# hw_system_switch.net
KiCad netlist of a schematic drawn in Altium Designer
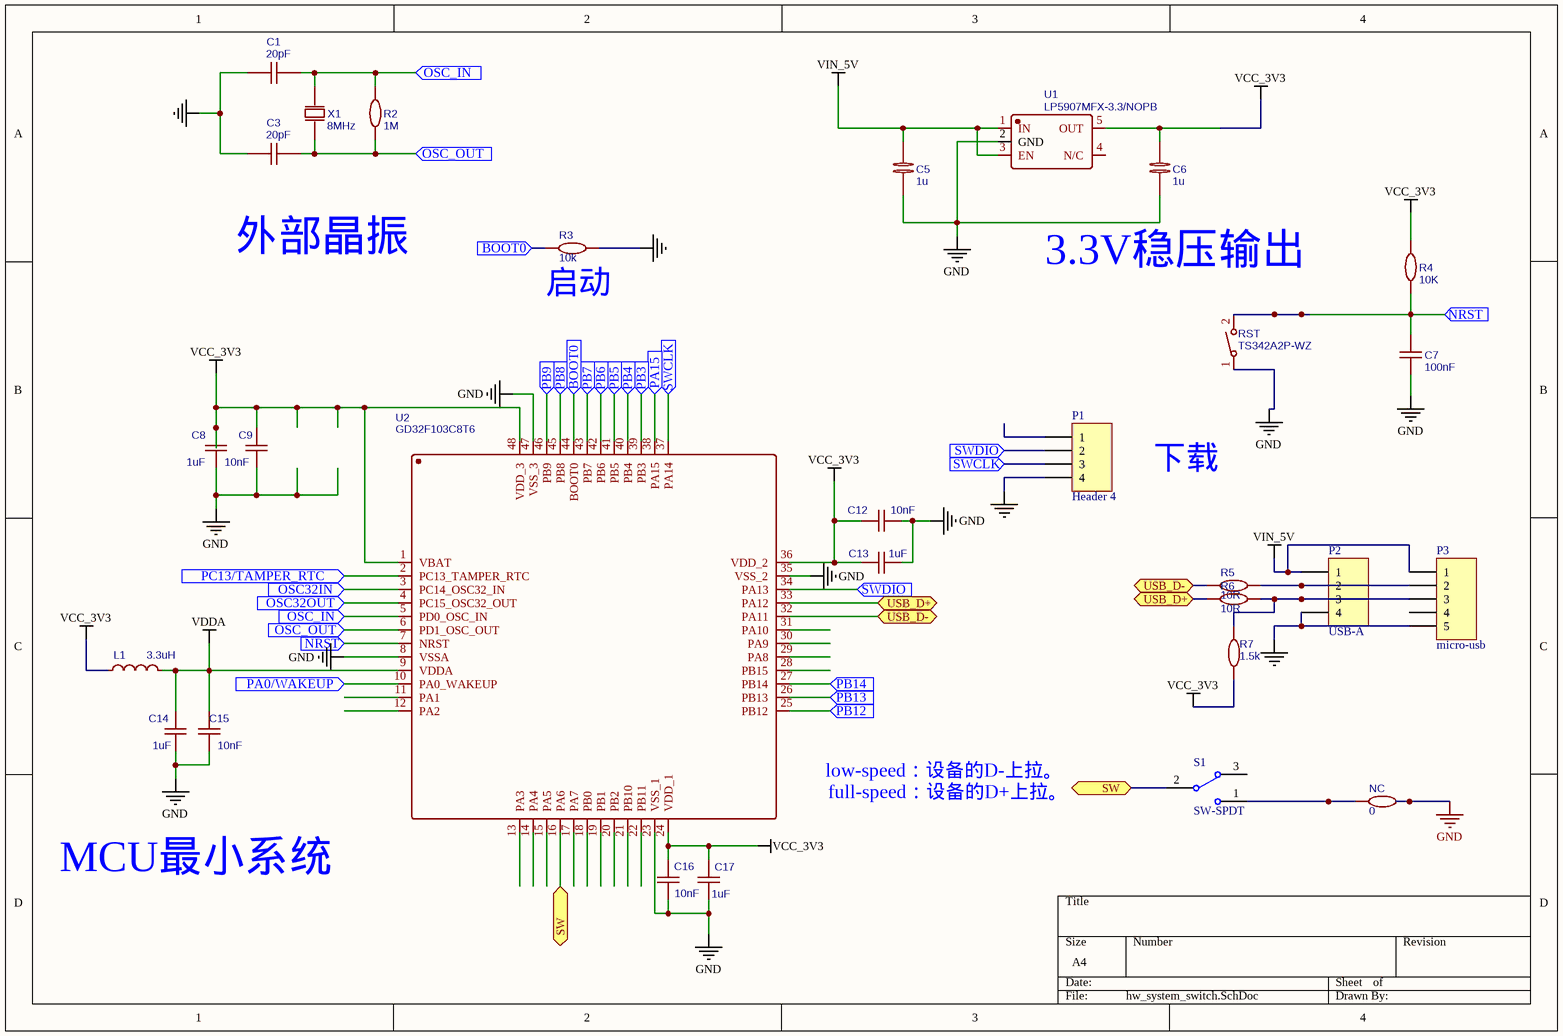
[diagram p0: hw_system_switch.SchDoc]

(export (version "E")
  (design (tool "Eeschema 10.0.6"))
  (components
    (comp (ref "C1")
      (value "20pF")
      (footprint "0603")
      (fields
        (field (name "BOM_MANUFACTURER PART") "0603CG200J500NT")
        (field (name "BOM_SUPPLIER PART") "C91702")
      )
      (libsource (lib "altium-import") (part "root_0_20pF_"))
    )
    (comp (ref "C3")
      (value "20pF")
      (footprint "0603")
      (fields
        (field (name "BOM_MANUFACTURER PART") "0603CG200J500NT")
        (field (name "BOM_SUPPLIER PART") "C91702")
      )
      (libsource (lib "altium-import") (part "root_0_20pF_"))
    )
    (comp (ref "C5")
      (value "1u")
      (footprint "0603")
      (fields (field (name "BOM_MANUFACTURER PART") "?"))
      (libsource (lib "altium-import") (part "root_0_1u_"))
    )
    (comp (ref "C6")
      (value "1u")
      (footprint "0603")
      (fields (field (name "BOM_MANUFACTURER PART") "?"))
      (libsource (lib "altium-import") (part "root_0_1u_"))
    )
    (comp (ref "C7")
      (value "100nF")
      (footprint "0603")
      (fields
        (field (name "BOM_MANUFACTURER PART") "0603B104K500NT")
        (field (name "BOM_SUPPLIER PART") "C30926")
      )
      (libsource (lib "altium-import") (part "root_1_100nF_"))
    )
    (comp (ref "C8")
      (value "1uF")
      (footprint "0603")
      (fields
        (field (name "BOM_MANUFACTURER PART") "CL10A105KP8NNNC")
        (field (name "BOM_SUPPLIER PART") "C26413")
      )
      (libsource (lib "") (part "root_1_1uF__1"))
    )
    (comp (ref "C9")
      (value "10nF")
      (footprint "0603")
      (fields
        (field (name "BOM_MANUFACTURER PART") "CC0603KRX7R9BB103")
        (field (name "BOM_SUPPLIER PART") "C100042")
      )
      (libsource (lib "altium-import") (part "root_1_10nF_"))
    )
    (comp (ref "C12")
      (value "10nF")
      (footprint "0603")
      (fields
        (field (name "BOM_MANUFACTURER PART") "CC0603KRX7R9BB103")
        (field (name "BOM_SUPPLIER PART") "C100042")
      )
      (libsource (lib "altium-import") (part "root_2_10nF_"))
    )
    (comp (ref "C13")
      (value "1uF")
      (footprint "0603")
      (fields
        (field (name "BOM_MANUFACTURER PART") "CL10A105KP8NNNC")
        (field (name "BOM_SUPPLIER PART") "C26413")
      )
      (libsource (lib "altium-import") (part "root_2_1uF_"))
    )
    (comp (ref "C14")
      (value "1uF")
      (footprint "0603")
      (fields
        (field (name "BOM_MANUFACTURER PART") "CL10A105KP8NNNC")
        (field (name "BOM_SUPPLIER PART") "C26413")
      )
      (libsource (lib "") (part "root_1_1uF__1"))
    )
    (comp (ref "C15")
      (value "10nF")
      (footprint "0603")
      (fields
        (field (name "BOM_MANUFACTURER PART") "CC0603KRX7R9BB103")
        (field (name "BOM_SUPPLIER PART") "C100042")
      )
      (libsource (lib "altium-import") (part "root_1_10nF_"))
    )
    (comp (ref "C16")
      (value "10nF")
      (footprint "0603")
      (fields
        (field (name "BOM_MANUFACTURER PART") "CC0603KRX7R9BB103")
        (field (name "BOM_SUPPLIER PART") "C100042")
      )
      (libsource (lib "") (part "root_1_10nF__1"))
    )
    (comp (ref "C17")
      (value "1uF")
      (footprint "0603")
      (fields
        (field (name "BOM_MANUFACTURER PART") "CL10A105KP8NNNC")
        (field (name "BOM_SUPPLIER PART") "C26413")
      )
      (libsource (lib "altium-import") (part "root_1_1uF_"))
    )
    (comp (ref "L1")
      (value "3.3uH")
      (footprint "C0805")
      (fields
        (field (name "BOM_MANUFACTURER PART") "CMI160808U3R3KT")
        (field (name "BOM_SUPPLIER PART") "C139209")
      )
      (libsource (lib "altium-import") (part "root_0_3.3uH_"))
    )
    (comp (ref "NC")
      (value "0")
      (footprint "0603")
      (fields
        (field (name "BOM_MANUFACTURER PART") "RC0603JR-071ML")
        (field (name "BOM_SUPPLIER PART") "C107698")
      )
      (libsource (lib "altium-import") (part "root_0_1M_"))
    )
    (comp (ref "P1")
      (value "Header 4")
      (footprint "HDR1X4")
      (description "Header, 4-Pin")
      (fields (field (name "PUBLISHER") "Altium Limited"))
      (libsource (lib "Miscellaneous Connectors") (part "Header 4"))
    )
    (comp (ref "P2")
      (value "USB-A")
      (footprint "USB-TH_U-G-04DD-W-4")
      (description "Header, 4-Pin")
      (fields (field (name "PUBLISHER") "Altium Limited"))
      (libsource (lib "Miscellaneous Connectors") (part "Header 4"))
    )
    (comp (ref "P3")
      (value "micro-usb")
      (footprint "MICRO-USB-SMD_U-F-M5DD-W-2-SUS")
      (description "Header, 5-Pin, Right Angle")
      (fields (field (name "PUBLISHER") "Altium Limited"))
      (libsource (lib "Miscellaneous Connectors") (part "Header 5H"))
    )
    (comp (ref "R2")
      (value "1M")
      (footprint "0603")
      (fields
        (field (name "BOM_MANUFACTURER PART") "RC0603JR-071ML")
        (field (name "BOM_SUPPLIER PART") "C107698")
      )
      (libsource (lib "altium-import") (part "root_1_1M_"))
    )
    (comp (ref "R3")
      (value "10k")
      (footprint "0603")
      (fields
        (field (name "BOM_MANUFACTURER PART") "RC0603JR-071ML")
        (field (name "BOM_SUPPLIER PART") "C107698")
      )
      (libsource (lib "altium-import") (part "root_2_1M_"))
    )
    (comp (ref "R4")
      (value "10K")
      (footprint "0603")
      (fields
        (field (name "BOM_MANUFACTURER PART") "RC0603JR-0710KL")
        (field (name "BOM_SUPPLIER PART") "C99198")
      )
      (libsource (lib "altium-import") (part "root_1_10K_"))
    )
    (comp (ref "R5")
      (value "10R")
      (footprint "0603")
      (fields
        (field (name "BOM_MANUFACTURER PART") "RC0603JR-071ML")
        (field (name "BOM_SUPPLIER PART") "C107698")
      )
      (libsource (lib "altium-import") (part "root_2_1M_"))
    )
    (comp (ref "R6")
      (value "10R")
      (footprint "0603")
      (fields
        (field (name "BOM_MANUFACTURER PART") "RC0603JR-071ML")
        (field (name "BOM_SUPPLIER PART") "C107698")
      )
      (libsource (lib "altium-import") (part "root_2_1M_"))
    )
    (comp (ref "R7")
      (value "1.5k")
      (footprint "0603")
      (fields
        (field (name "BOM_MANUFACTURER PART") "RC0603JR-071ML")
        (field (name "BOM_SUPPLIER PART") "C107698")
      )
      (libsource (lib "altium-import") (part "root_3_1M_"))
    )
    (comp (ref "RST")
      (value "TS342A2P-WZ")
      (footprint "SW-SMD_L4.0-W2.9-LS5.0")
      (fields (field (name "BOM_SUPPLIER PART") "C557591") (field (name "CONTRIBUTOR") "LCSC"))
      (libsource (lib "altium-import") (part "root_1_TS342A2P-WZ_"))
    )
    (comp (ref "S1")
      (value "SW-SPDT")
      (footprint "PCBComponent_1")
      (description "SPDT Subminiature Toggle Switch, Right Angle Mounting, Vertical Actuation")
      (fields (field (name "PUBLISHER") "Altium Limited"))
      (libsource (lib "Miscellaneous Devices") (part "SW-SPDT"))
    )
    (comp (ref "U1")
      (value "LP5907MFX-3.3/NOPB")
      (footprint "SOT-23-5")
      (fields (field (name "BOM_SUPPLIER PART") "C80670") (field (name "CONTRIBUTOR") "LCSC"))
      (libsource (lib "altium-import") (part "root_0_LP5907MFX-3.3/NOPB_"))
    )
    (comp (ref "U2")
      (value "GD32F103C8T6")
      (footprint "TQFP-48_L7.0-W7.0-P0.50-LS9.0-BL")
      (fields (field (name "BOM_SUPPLIER PART") "C77994"))
      (libsource (lib "altium-import") (part "root_0_GD32F103C8T6_"))
    )
    (comp (ref "X1")
      (value "8MHz")
      (footprint "OSC-SMD_L5.0-W3.2")
      (fields
        (field (name "BOM_MANUFACTURER PART") "X49SD8MSD2SC")
        (field (name "BOM_SUPPLIER PART") "C21263")
      )
      (libsource (lib "altium-import") (part "root_1_8MHz_"))
    )
  )
  (nets
    (net (code "1") (name "/BOOT0") (class "Default")
      (node (ref "R3") (pin "2") (pinfunction "2_2") (pintype "passive"))
      (node (ref "U2") (pin "44") (pinfunction "BOOT0_44") (pintype "passive"))
    )
    (net (code "2") (name "/NRST") (class "Default")
      (node (ref "C7") (pin "2") (pinfunction "2_2") (pintype "passive"))
      (node (ref "R4") (pin "1") (pinfunction "1_1") (pintype "passive"))
      (node (ref "RST") (pin "2") (pinfunction "2_2") (pintype "passive"))
      (node (ref "U2") (pin "7") (pinfunction "NRST_7") (pintype "passive"))
    )
    (net (code "3") (name "/OSC32IN") (class "Default")
      (node (ref "U2") (pin "3") (pinfunction "PC14_OSC32_IN_3") (pintype "passive"))
    )
    (net (code "4") (name "/OSC32OUT") (class "Default")
      (node (ref "U2") (pin "4") (pinfunction "PC15_OSC32_OUT_4") (pintype "passive"))
    )
    (net (code "5") (name "/OSC_IN") (class "Default")
      (node (ref "C1") (pin "2") (pinfunction "2_2") (pintype "passive"))
      (node (ref "R2") (pin "2") (pinfunction "2_2") (pintype "passive"))
      (node (ref "U2") (pin "5") (pinfunction "PD0_OSC_IN_5") (pintype "passive"))
      (node (ref "X1") (pin "1") (pinfunction "OSC1_1") (pintype "passive"))
    )
    (net (code "6") (name "/OSC_OUT") (class "Default")
      (node (ref "C3") (pin "2") (pinfunction "2_2") (pintype "passive"))
      (node (ref "R2") (pin "1") (pinfunction "1_1") (pintype "passive"))
      (node (ref "U2") (pin "6") (pinfunction "PD1_OSC_OUT_6") (pintype "passive"))
      (node (ref "X1") (pin "2") (pinfunction "OSC2_2") (pintype "passive"))
    )
    (net (code "7") (name "/PA0{slash}WAKEUP") (class "Default")
      (node (ref "U2") (pin "10") (pinfunction "PA0_WAKEUP_10") (pintype "passive"))
    )
    (net (code "8") (name "/PA15") (class "Default")
      (node (ref "U2") (pin "38") (pinfunction "PA15_38") (pintype "passive"))
    )
    (net (code "9") (name "/PB3") (class "Default")
      (node (ref "U2") (pin "39") (pinfunction "PB3_39") (pintype "passive"))
    )
    (net (code "10") (name "/PB4") (class "Default")
      (node (ref "U2") (pin "40") (pinfunction "PB4_40") (pintype "passive"))
    )
    (net (code "11") (name "/PB5") (class "Default")
      (node (ref "U2") (pin "41") (pinfunction "PB5_41") (pintype "passive"))
    )
    (net (code "12") (name "/PB6") (class "Default")
      (node (ref "U2") (pin "42") (pinfunction "PB6_42") (pintype "passive"))
    )
    (net (code "13") (name "/PB7") (class "Default")
      (node (ref "U2") (pin "43") (pinfunction "PB7_43") (pintype "passive"))
    )
    (net (code "14") (name "/PB8") (class "Default")
      (node (ref "U2") (pin "45") (pinfunction "PB8_45") (pintype "passive"))
    )
    (net (code "15") (name "/PB9") (class "Default")
      (node (ref "U2") (pin "46") (pinfunction "PB9_46") (pintype "passive"))
    )
    (net (code "16") (name "/PB12") (class "Default")
      (node (ref "U2") (pin "25") (pinfunction "PB12_25") (pintype "passive"))
    )
    (net (code "17") (name "/PB13") (class "Default")
      (node (ref "U2") (pin "26") (pinfunction "PB13_26") (pintype "passive"))
    )
    (net (code "18") (name "/PB14") (class "Default")
      (node (ref "U2") (pin "27") (pinfunction "PB14_27") (pintype "passive"))
    )
    (net (code "19") (name "/PC13{slash}TAMPER_RTC") (class "Default")
      (node (ref "U2") (pin "2") (pinfunction "PC13_TAMPER_RTC_2") (pintype "passive"))
    )
    (net (code "20") (name "/SW") (class "Default")
      (node (ref "S1") (pin "2") (pinfunction "2_2") (pintype "passive"))
      (node (ref "U2") (pin "16") (pinfunction "PA6_16") (pintype "passive"))
    )
    (net (code "21") (name "/SWCLK") (class "Default")
      (node (ref "P1") (pin "3") (pinfunction "3_3") (pintype "passive"))
      (node (ref "U2") (pin "37") (pinfunction "PA14_37") (pintype "passive"))
    )
    (net (code "22") (name "/SWDIO") (class "Default")
      (node (ref "P1") (pin "2") (pinfunction "2_2") (pintype "passive"))
      (node (ref "U2") (pin "34") (pinfunction "PA13_34") (pintype "passive"))
    )
    (net (code "23") (name "/USB_D+") (class "Default")
      (node (ref "R6") (pin "2") (pinfunction "2_2") (pintype "passive"))
      (node (ref "U2") (pin "33") (pinfunction "PA12_33") (pintype "passive"))
    )
    (net (code "24") (name "/USB_D-") (class "Default")
      (node (ref "R5") (pin "2") (pinfunction "2_2") (pintype "passive"))
      (node (ref "U2") (pin "32") (pinfunction "PA11_32") (pintype "passive"))
    )
    (net (code "25") (name "GND") (class "Default")
      (node (ref "C1") (pin "1") (pinfunction "1_1") (pintype "passive"))
      (node (ref "C12") (pin "1") (pinfunction "1_1") (pintype "passive"))
      (node (ref "C13") (pin "1") (pinfunction "1_1") (pintype "passive"))
      (node (ref "C14") (pin "1") (pinfunction "1_1") (pintype "passive"))
      (node (ref "C15") (pin "1") (pinfunction "1_1") (pintype "passive"))
      (node (ref "C16") (pin "1") (pinfunction "1_1") (pintype "passive"))
      (node (ref "C17") (pin "1") (pinfunction "1_1") (pintype "passive"))
      (node (ref "C3") (pin "1") (pinfunction "1_1") (pintype "passive"))
      (node (ref "C5") (pin "2") (pinfunction "2_2") (pintype "passive"))
      (node (ref "C6") (pin "2") (pinfunction "2_2") (pintype "passive"))
      (node (ref "C7") (pin "1") (pinfunction "1_1") (pintype "passive"))
      (node (ref "C8") (pin "1") (pinfunction "1_1") (pintype "passive"))
      (node (ref "C9") (pin "1") (pinfunction "1_1") (pintype "passive"))
      (node (ref "NC") (pin "2") (pinfunction "2_2") (pintype "passive"))
      (node (ref "P1") (pin "4") (pinfunction "4_4") (pintype "passive"))
      (node (ref "P2") (pin "4") (pinfunction "4_4") (pintype "passive"))
      (node (ref "P3") (pin "5") (pinfunction "5_5") (pintype "passive"))
      (node (ref "R3") (pin "1") (pinfunction "1_1") (pintype "passive"))
      (node (ref "RST") (pin "1") (pinfunction "1_1") (pintype "passive"))
      (node (ref "U1") (pin "2") (pinfunction "GND_2") (pintype "passive"))
      (node (ref "U2") (pin "23") (pinfunction "VSS_1_23") (pintype "passive"))
      (node (ref "U2") (pin "35") (pinfunction "VSS_2_35") (pintype "passive"))
      (node (ref "U2") (pin "47") (pinfunction "VSS_3_47") (pintype "passive"))
      (node (ref "U2") (pin "8") (pinfunction "VSSA_8") (pintype "passive"))
    )
    (net (code "26") (name "Net-(NC-Pad1)") (class "Default")
      (node (ref "NC") (pin "1") (pinfunction "1_1") (pintype "passive"))
      (node (ref "S1") (pin "1") (pinfunction "1_1") (pintype "passive"))
    )
    (net (code "27") (name "Net-(P2-Pad2)") (class "Default")
      (node (ref "P2") (pin "2") (pinfunction "2_2") (pintype "passive"))
      (node (ref "P3") (pin "2") (pinfunction "2_2") (pintype "passive"))
      (node (ref "R5") (pin "1") (pinfunction "1_1") (pintype "passive"))
    )
    (net (code "28") (name "Net-(P2-Pad3)") (class "Default")
      (node (ref "P2") (pin "3") (pinfunction "3_3") (pintype "passive"))
      (node (ref "P3") (pin "3") (pinfunction "3_3") (pintype "passive"))
      (node (ref "R6") (pin "1") (pinfunction "1_1") (pintype "passive"))
      (node (ref "R7") (pin "1") (pinfunction "1_1") (pintype "passive"))
    )
    (net (code "29") (name "VCC_3V3") (class "Default")
      (node (ref "C12") (pin "2") (pinfunction "2_2") (pintype "passive"))
      (node (ref "C13") (pin "2") (pinfunction "2_2") (pintype "passive"))
      (node (ref "C16") (pin "2") (pinfunction "2_2") (pintype "passive"))
      (node (ref "C17") (pin "2") (pinfunction "2_2") (pintype "passive"))
      (node (ref "C6") (pin "1") (pinfunction "1_1") (pintype "passive"))
      (node (ref "C8") (pin "2") (pinfunction "2_2") (pintype "passive"))
      (node (ref "C9") (pin "2") (pinfunction "2_2") (pintype "passive"))
      (node (ref "L1") (pin "2") (pinfunction "2_2") (pintype "passive"))
      (node (ref "R4") (pin "2") (pinfunction "2_2") (pintype "passive"))
      (node (ref "R7") (pin "2") (pinfunction "2_2") (pintype "passive"))
      (node (ref "U1") (pin "5") (pinfunction "OUT_5") (pintype "passive"))
      (node (ref "U2") (pin "1") (pinfunction "VBAT_1") (pintype "passive"))
      (node (ref "U2") (pin "24") (pinfunction "VDD_1_24") (pintype "passive"))
      (node (ref "U2") (pin "36") (pinfunction "VDD_2_36") (pintype "passive"))
      (node (ref "U2") (pin "48") (pinfunction "VDD_3_48") (pintype "passive"))
    )
    (net (code "30") (name "VDDA") (class "Default")
      (node (ref "C14") (pin "2") (pinfunction "2_2") (pintype "passive"))
      (node (ref "C15") (pin "2") (pinfunction "2_2") (pintype "passive"))
      (node (ref "L1") (pin "1") (pinfunction "1_1") (pintype "passive"))
      (node (ref "U2") (pin "9") (pinfunction "VDDA_9") (pintype "passive"))
    )
    (net (code "31") (name "VIN_5V") (class "Default")
      (node (ref "C5") (pin "1") (pinfunction "1_1") (pintype "passive"))
      (node (ref "P2") (pin "1") (pinfunction "1_1") (pintype "passive"))
      (node (ref "P3") (pin "1") (pinfunction "1_1") (pintype "passive"))
      (node (ref "U1") (pin "1") (pinfunction "IN_1") (pintype "passive"))
      (node (ref "U1") (pin "3") (pinfunction "EN_3") (pintype "passive"))
    )
    (net (code "32") (name "unconnected-(P1-Pad1)") (class "Default")
      (node (ref "P1") (pin "1") (pinfunction "1_1") (pintype "passive"))
    )
    (net (code "33") (name "unconnected-(P3-Pad4)") (class "Default")
      (node (ref "P3") (pin "4") (pinfunction "4_4") (pintype "passive"))
    )
    (net (code "34") (name "unconnected-(S1-Pad3)") (class "Default")
      (node (ref "S1") (pin "3") (pinfunction "3_3") (pintype "passive"))
    )
    (net (code "35") (name "unconnected-(U1-N{slash}C-Pad4)") (class "Default")
      (node (ref "U1") (pin "4") (pinfunction "N/C_4") (pintype "passive"))
    )
    (net (code "36") (name "unconnected-(U2-PA1-Pad11)") (class "Default")
      (node (ref "U2") (pin "11") (pinfunction "PA1_11") (pintype "passive"))
    )
    (net (code "37") (name "unconnected-(U2-PA2-Pad12)") (class "Default")
      (node (ref "U2") (pin "12") (pinfunction "PA2_12") (pintype "passive"))
    )
    (net (code "38") (name "unconnected-(U2-PA3-Pad13)") (class "Default")
      (node (ref "U2") (pin "13") (pinfunction "PA3_13") (pintype "passive"))
    )
    (net (code "39") (name "unconnected-(U2-PA4-Pad14)") (class "Default")
      (node (ref "U2") (pin "14") (pinfunction "PA4_14") (pintype "passive"))
    )
    (net (code "40") (name "unconnected-(U2-PA5-Pad15)") (class "Default")
      (node (ref "U2") (pin "15") (pinfunction "PA5_15") (pintype "passive"))
    )
    (net (code "41") (name "unconnected-(U2-PA7-Pad17)") (class "Default")
      (node (ref "U2") (pin "17") (pinfunction "PA7_17") (pintype "passive"))
    )
    (net (code "42") (name "unconnected-(U2-PA8-Pad29)") (class "Default")
      (node (ref "U2") (pin "29") (pinfunction "PA8_29") (pintype "passive"))
    )
    (net (code "43") (name "unconnected-(U2-PA9-Pad30)") (class "Default")
      (node (ref "U2") (pin "30") (pinfunction "PA9_30") (pintype "passive"))
    )
    (net (code "44") (name "unconnected-(U2-PA10-Pad31)") (class "Default")
      (node (ref "U2") (pin "31") (pinfunction "PA10_31") (pintype "passive"))
    )
    (net (code "45") (name "unconnected-(U2-PB0-Pad18)") (class "Default")
      (node (ref "U2") (pin "18") (pinfunction "PB0_18") (pintype "passive"))
    )
    (net (code "46") (name "unconnected-(U2-PB1-Pad19)") (class "Default")
      (node (ref "U2") (pin "19") (pinfunction "PB1_19") (pintype "passive"))
    )
    (net (code "47") (name "unconnected-(U2-PB2-Pad20)") (class "Default")
      (node (ref "U2") (pin "20") (pinfunction "PB2_20") (pintype "passive"))
    )
    (net (code "48") (name "unconnected-(U2-PB10-Pad21)") (class "Default")
      (node (ref "U2") (pin "21") (pinfunction "PB10_21") (pintype "passive"))
    )
    (net (code "49") (name "unconnected-(U2-PB11-Pad22)") (class "Default")
      (node (ref "U2") (pin "22") (pinfunction "PB11_22") (pintype "passive"))
    )
    (net (code "50") (name "unconnected-(U2-PB15-Pad28)") (class "Default")
      (node (ref "U2") (pin "28") (pinfunction "PB15_28") (pintype "passive"))
    )
  )
)
